# Sheet1.net
KiCad netlist of a schematic drawn in Altium Designer
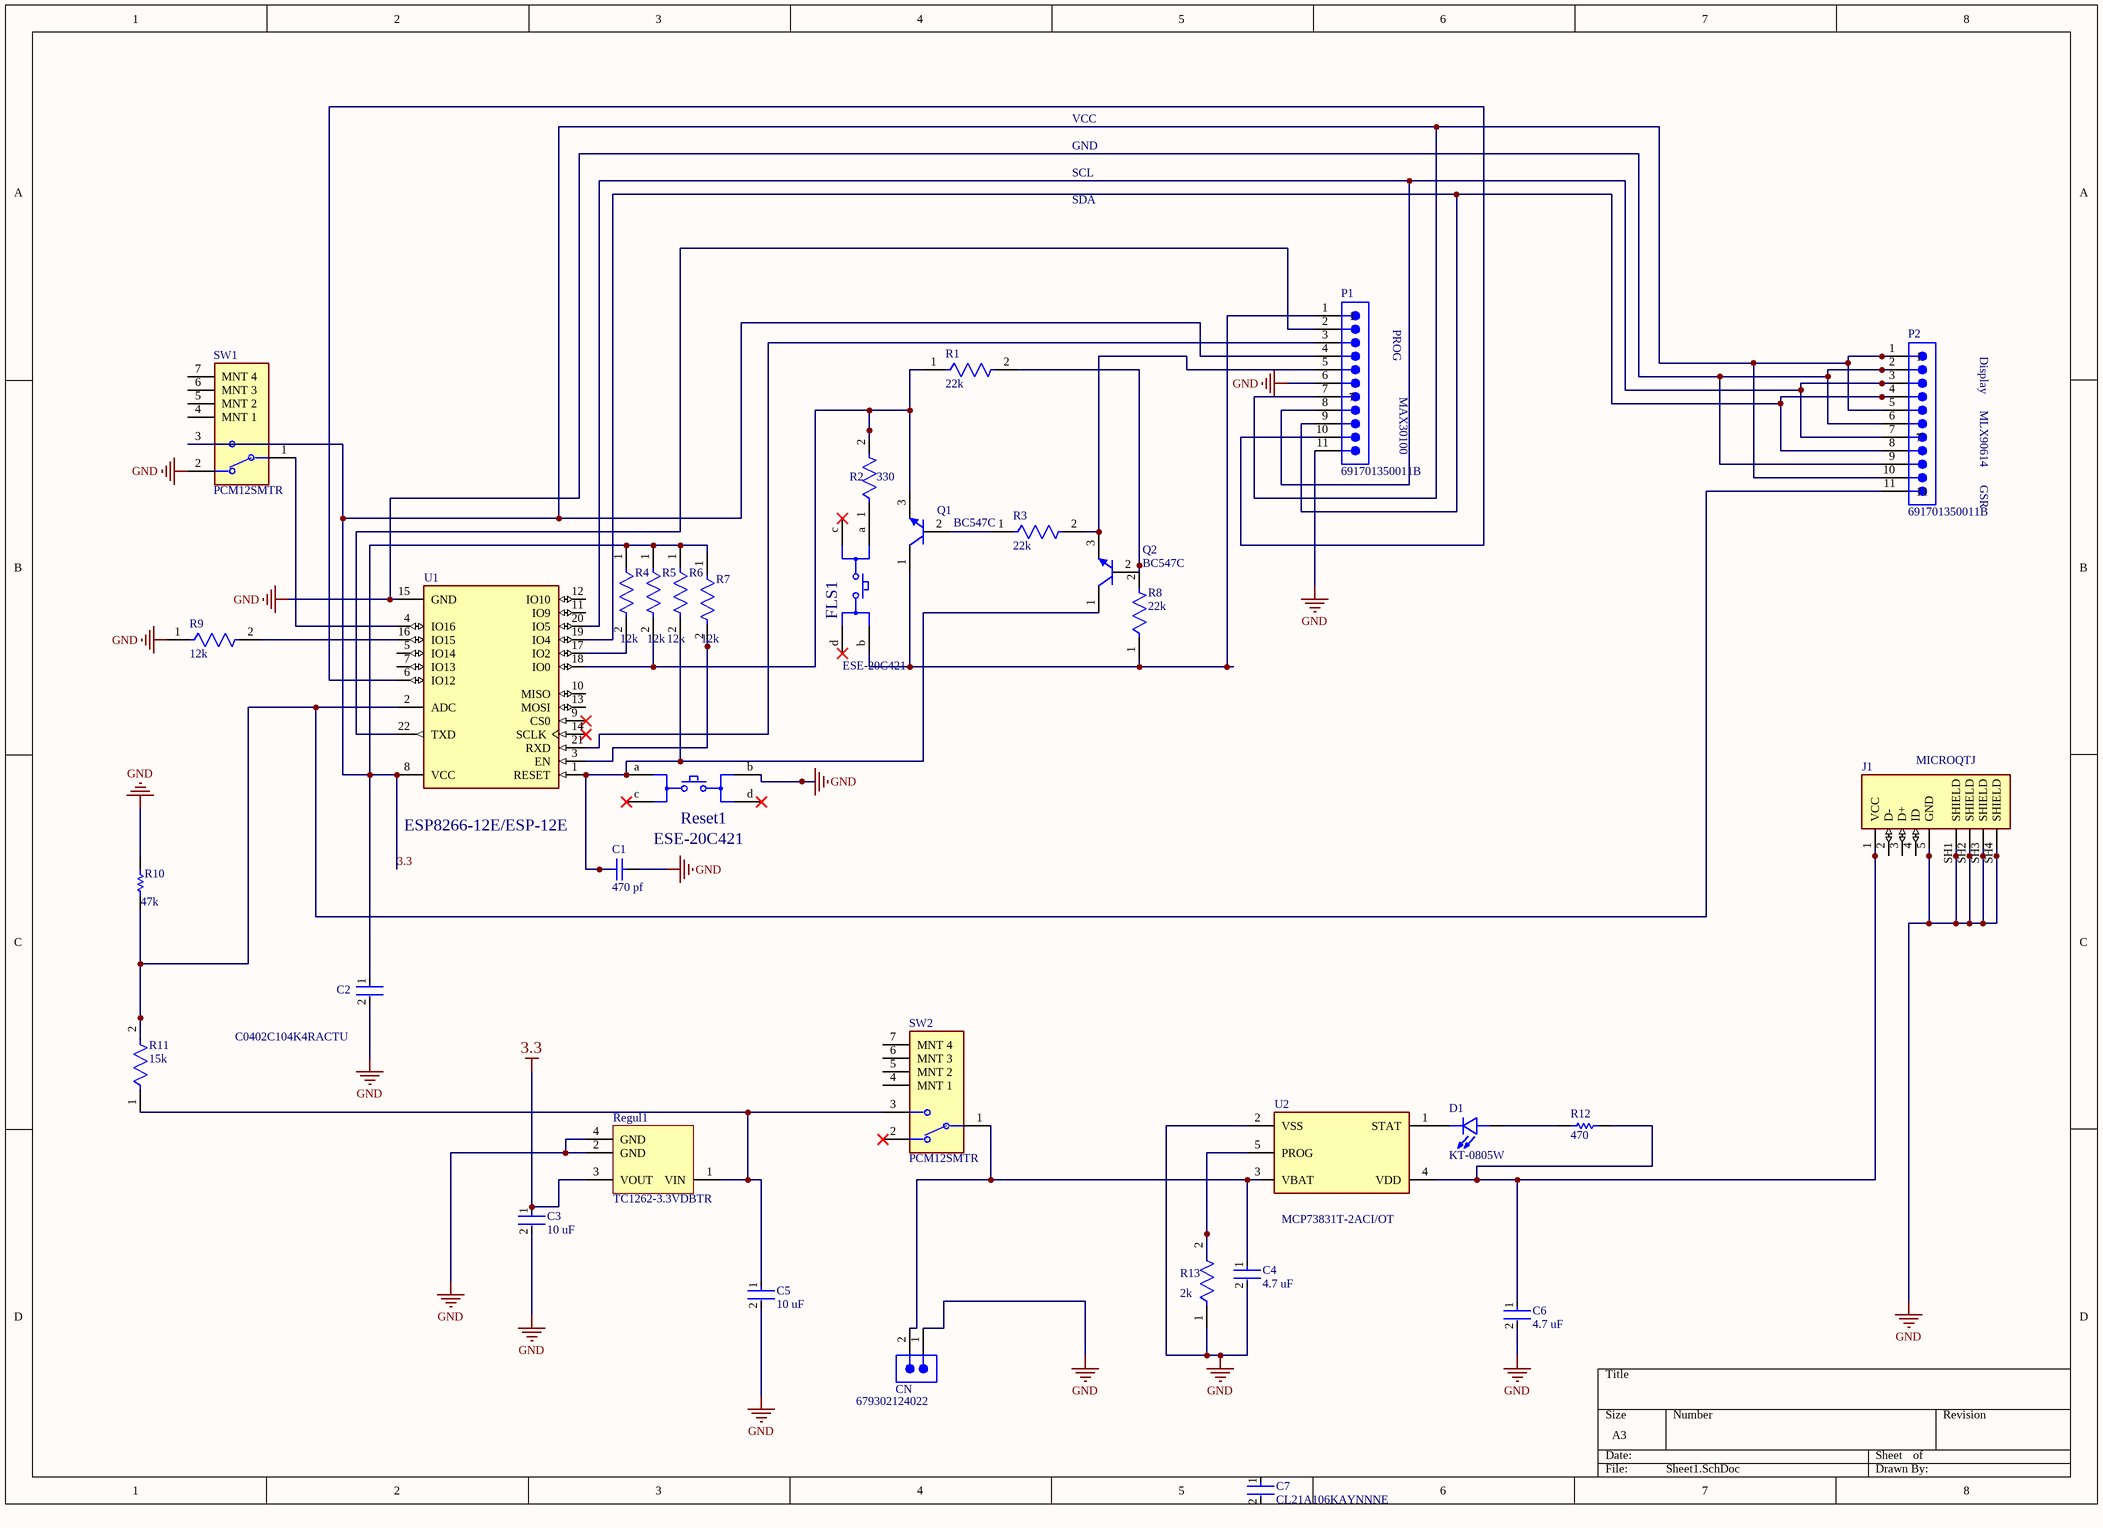
[diagram p0: Sheet1.SchDoc]

(export (version "E")
  (design (tool "Eeschema 10.0.6"))
  (components
    (comp (ref "C1")
      (value "470 pf")
      (footprint "CAPC2013X135X50LL15T20")
      (fields (field (name "MANUFACTURER") "Vitramon") (field (name "PART NUMBER") "VJ0805Y472KXACW1BC"))
      (libsource (lib "Altium Content Vault") (part "CAP"))
    )
    (comp (ref "C2")
      (value "C0402C104K4RACTU")
      (footprint "FP-C0402-BB-MFG")
      (description "CAP CER 0.1UF 16V X7R 0402")
      (fields
        (field (name "TOLERANCE") "0.1")
        (field (name "OCTOPART") "https://octopart.com/c0402c104k4ractu-kemet-94158")
      )
      (libsource (lib "Altium Content Vault") (part "b4654b650e69147ec39a6b967a45e02"))
    )
    (comp (ref "C3")
      (value "10 uF")
      (footprint "FP-CL21-IPC_A")
      (description "CL21 Series 0805 10uF 25V ±10% Tolerance X5R Multilayer Ceramic Chip Capacitor")
      (fields (field (name "TOLERANCE") "10%"))
      (libsource (lib "Altium Content Vault") (part "b4654b650e69147ec39a6b967a45e02"))
    )
    (comp (ref "C4")
      (value "4.7 uF")
      (footprint "FP-CL21-IPC_A")
      (description "CL21 Series 0805 4.7uF 25V ±10% Tolerance X5R Multilayer Ceramic Chip Capacitor")
      (fields (field (name "TOLERANCE") "10%"))
      (libsource (lib "Altium Content Vault") (part "b4654b650e69147ec39a6b967a45e02"))
    )
    (comp (ref "C5")
      (value "10 uF")
      (footprint "FP-CL21-IPC_A")
      (description "CL21 Series 0805 10uF 25V ±10% Tolerance X5R Multilayer Ceramic Chip Capacitor")
      (fields (field (name "TOLERANCE") "10%"))
      (libsource (lib "Altium Content Vault") (part "b4654b650e69147ec39a6b967a45e02"))
    )
    (comp (ref "C6")
      (value "4.7 uF")
      (footprint "FP-CL21-IPC_A")
      (description "CL21 Series 0805 4.7uF 25V ±10% Tolerance X5R Multilayer Ceramic Chip Capacitor")
      (fields (field (name "TOLERANCE") "10%"))
      (libsource (lib "Altium Content Vault") (part "b4654b650e69147ec39a6b967a45e02"))
    )
    (comp (ref "C7")
      (value "CL21A106KAYNNNE")
      (footprint "FP-CL21-IPC_A")
      (description "CL21 Series 0805 10uF 25V ±10% Tolerance X5R Multilayer Ceramic Chip Capacitor")
      (fields (field (name "TOLERANCE") "10%"))
      (libsource (lib "Altium Content Vault") (part "b4654b650e69147ec39a6b967a45e02"))
    )
    (comp (ref "CN")
      (value "679302124022")
      (footprint "679302124022")
      (libsource (lib "Altium Content Vault") (part "Header_Male_1R_02P"))
    )
    (comp (ref "D1")
      (value "KT-0805W")
      (footprint "LED_KT-0805W")
      (description "Light Emitting Diodes")
      (fields (field (name "MF") "Hubei KENTO Elec"))
      (libsource (lib "KT-0805W") (part "KT-0805W"))
    )
    (comp (ref "FLS1")
      (value "ESE-20C421")
      (footprint "FP-ESE-20C421-MFG")
      (description "SWITCH PUSH SPST-NO 0.1A 14V")
      (libsource (lib "Altium Content Vault") (part "eb2d96918082f90afa573f5ab447b27"))
    )
    (comp (ref "J1")
      (value "MICROQTJ")
      (footprint "SHOUHAN_MICROQTJ")
      (fields (field (name "MF") "shou han"))
      (libsource (lib "MICROQTJ") (part "MICROQTJ"))
    )
    (comp (ref "P1")
      (value "691701350011B")
      (footprint "691701350011B")
      (libsource (lib "Altium Content Vault") (part "TBL - 1R - 11P - Male"))
    )
    (comp (ref "P2")
      (value "691701350011B")
      (footprint "691701350011B")
      (libsource (lib "Altium Content Vault") (part "TBL - 1R - 11P - Male"))
    )
    (comp (ref "Q1")
      (value "BC547C")
      (footprint "ONSC-TO-92-3-29-11")
      (description "Amplifier Transistor, NPN Silicon, 3-Pin TO-92, Bulk Box")
      (fields (field (name "MANUFACTURER") "On Semiconductor"))
      (libsource (lib "Altium Content Vault") (part "ONSC-NPN-C1B2E3-3"))
    )
    (comp (ref "Q2")
      (value "BC547C")
      (footprint "ONSC-TO-92-3-29-11")
      (description "Amplifier Transistor, NPN Silicon, 3-Pin TO-92, Bulk Box")
      (fields (field (name "MANUFACTURER") "On Semiconductor"))
      (libsource (lib "Altium Content Vault") (part "ONSC-NPN-C1B2E3-3"))
    )
    (comp (ref "R1")
      (value "22k")
      (footprint "FP-CRCW0603-e3-IPC_B")
      (description "RES Thick Film, 22kΩ, 1%, 0.1W, 100ppm/°C, 0603")
      (fields (field (name "TOLERANCE") "1%"))
      (libsource (lib "Altium Content Vault") (part "1029c3af85768c4190bb7ad29bc67b5"))
    )
    (comp (ref "R2")
      (value "330")
      (footprint "FP-CRCW0402-e3-IPC_C")
      (description "RES Thick Film, 330kΩ, 1%, 0.063W, 100ppm/°C, 0402")
      (fields (field (name "TOLERANCE") "1%"))
      (libsource (lib "Altium Content Vault") (part "1029c3af85768c4190bb7ad29bc67b5"))
    )
    (comp (ref "R3")
      (value "22k")
      (footprint "FP-CRCW0603-e3-IPC_B")
      (description "RES Thick Film, 22kΩ, 1%, 0.1W, 100ppm/°C, 0603")
      (fields (field (name "TOLERANCE") "1%"))
      (libsource (lib "Altium Content Vault") (part "1029c3af85768c4190bb7ad29bc67b5"))
    )
    (comp (ref "R4")
      (value "12k")
      (footprint "FP-CRCW0603-e3-IPC_A")
      (description "RES Thick Film, 12kΩ, 1%, 0.1W, 100ppm/°C, 0603")
      (fields (field (name "TOLERANCE") "1%"))
      (libsource (lib "Altium Content Vault") (part "1029c3af85768c4190bb7ad29bc67b5"))
    )
    (comp (ref "R5")
      (value "12k")
      (footprint "FP-CRCW0603-e3-IPC_A")
      (description "RES Thick Film, 12kΩ, 1%, 0.1W, 100ppm/°C, 0603")
      (fields (field (name "TOLERANCE") "1%"))
      (libsource (lib "Altium Content Vault") (part "1029c3af85768c4190bb7ad29bc67b5"))
    )
    (comp (ref "R6")
      (value "12k")
      (footprint "FP-CRCW0603-e3-IPC_A")
      (description "RES Thick Film, 12kΩ, 1%, 0.1W, 100ppm/°C, 0603")
      (fields (field (name "TOLERANCE") "1%"))
      (libsource (lib "Altium Content Vault") (part "1029c3af85768c4190bb7ad29bc67b5"))
    )
    (comp (ref "R7")
      (value "12k")
      (footprint "FP-CRCW0603-e3-IPC_A")
      (description "RES Thick Film, 12kΩ, 1%, 0.1W, 100ppm/°C, 0603")
      (fields (field (name "TOLERANCE") "1%"))
      (libsource (lib "Altium Content Vault") (part "1029c3af85768c4190bb7ad29bc67b5"))
    )
    (comp (ref "R8")
      (value "22k")
      (footprint "FP-CRCW0603-e3-IPC_B")
      (description "RES Thick Film, 22kΩ, 1%, 0.1W, 100ppm/°C, 0603")
      (fields (field (name "TOLERANCE") "1%"))
      (libsource (lib "Altium Content Vault") (part "1029c3af85768c4190bb7ad29bc67b5"))
    )
    (comp (ref "R9")
      (value "12k")
      (footprint "FP-CRCW0603-e3-IPC_A")
      (description "RES Thick Film, 12kΩ, 1%, 0.1W, 100ppm/°C, 0603")
      (fields (field (name "TOLERANCE") "1%"))
      (libsource (lib "Altium Content Vault") (part "1029c3af85768c4190bb7ad29bc67b5"))
    )
    (comp (ref "R10")
      (value "47k")
      (footprint "RESC2013X70X40ML20T20")
      (fields (field (name "MANUFACTURER") "Panasonic") (field (name "PART NUMBER") "ERJ-6GEYJ473V"))
      (libsource (lib "Altium Content Vault") (part "RES"))
    )
    (comp (ref "R11")
      (value "15k")
      (footprint "FP-CRCW0805-e3-IPC_C")
      (description "RES Thick Film, 15kΩ, 1%, 0.125W, 100ppm/°C, 0805")
      (fields (field (name "TOLERANCE") "1%"))
      (libsource (lib "Altium Content Vault") (part "1029c3af85768c4190bb7ad29bc67b5"))
    )
    (comp (ref "R12")
      (value "470")
      (footprint "RESC2013X60X35LL10T20")
      (description "Chip Resistor, 470 Ohm, +/- 1%, 125 mW, -55 to 155 degC, 0805 (2012 Metric), RoHS, Tape and Reel")
      (fields (field (name "MANUFACTURER") "Yageo"))
      (libsource (lib "Altium Content Vault") (part "RES-2"))
    )
    (comp (ref "R13")
      (value "2k")
      (footprint "FP-AC0603-IPC_B")
      (description "RES 2kΩ 1.00% 0.1W 0603")
      (fields (field (name "TOLERANCE") "1%"))
      (libsource (lib "Altium Content Vault") (part "1029c3af85768c4190bb7ad29bc67b5"))
    )
    (comp (ref "Regul1")
      (value "TC1262-3.3VDBTR")
      (footprint "SOT-223-DB3_M")
      (description "500mA Fixed Output CMOS LDO, 3-Pin SOT-223, Extended Temperature, Tape and Reel")
      (libsource (lib "Altium Content Vault") (part "PM-LINEREG-TC1262-IL4"))
    )
    (comp (ref "Reset1")
      (value "ESE-20C421")
      (footprint "FP-ESE-20C421-MFG")
      (description "SWITCH PUSH SPST-NO 0.1A 14V")
      (libsource (lib "Altium Content Vault") (part "eb2d96918082f90afa573f5ab447b27"))
    )
    (comp (ref "SW1")
      (value "PCM12SMTR")
      (footprint "FP-PCM12SMTR-MFG")
      (description "SWITCH SLIDE SPDT 300MA 6V")
      (libsource (lib "Altium Content Vault") (part "1a3f67d7e2b5469b171eeab59ffb4d2"))
    )
    (comp (ref "SW2")
      (value "PCM12SMTR")
      (footprint "FP-PCM12SMTR-MFG")
      (description "SWITCH SLIDE SPDT 300MA 6V")
      (libsource (lib "Altium Content Vault") (part "1a3f67d7e2b5469b171eeab59ffb4d2"))
    )
    (comp (ref "U1")
      (value "ESP8266-12E/ESP-12E")
      (footprint "XCVR_ESP8266-12E/ESP-12E")
      (fields (field (name "MF") "AI-Thinker"))
      (libsource (lib "ESP8266-12E_ESP-12E (1)") (part "ESP8266-12E/ESP-12E"))
    )
    (comp (ref "U2")
      (value "MCP73831T-2ACI/OT")
      (footprint "FP-C04-091-OT-IPC_B")
      (description "IC CONTROLLR LI-ION 4.2V SOT23-5")
      (libsource (lib "Altium Content Vault") (part "61f5a3bb3429d9e0caadea342aa3b19"))
    )
  )
  (nets
    (net (code "1") (name "3.3") (class "Default")
      (node (ref "C2") (pin "1") (pinfunction "1_1") (pintype "passive"))
      (node (ref "C3") (pin "1") (pinfunction "1_1") (pintype "passive"))
      (node (ref "P1") (pin "4") (pinfunction "4_4") (pintype "passive"))
      (node (ref "P1") (pin "7") (pinfunction "7_7") (pintype "passive"))
      (node (ref "P2") (pin "1") (pinfunction "1_1") (pintype "passive"))
      (node (ref "P2") (pin "10") (pinfunction "10_10") (pintype "passive"))
      (node (ref "P2") (pin "5") (pinfunction "5_5") (pintype "passive"))
      (node (ref "R4") (pin "1") (pinfunction "1_1") (pintype "passive"))
      (node (ref "R5") (pin "1") (pinfunction "1_1") (pintype "passive"))
      (node (ref "R6") (pin "1") (pinfunction "1_1") (pintype "passive"))
      (node (ref "R7") (pin "1") (pinfunction "1_1") (pintype "passive"))
      (node (ref "Regul1") (pin "3") (pinfunction "VOUT_3") (pintype "power_in"))
      (node (ref "SW1") (pin "3") (pinfunction "3_3") (pintype "passive"))
      (node (ref "U1") (pin "8") (pinfunction "VCC_8") (pintype "power_in"))
    )
    (net (code "2") (name "GND") (class "Default")
      (node (ref "C1") (pin "2") (pinfunction "2_2") (pintype "passive"))
      (node (ref "C2") (pin "2") (pinfunction "2_2") (pintype "passive"))
      (node (ref "C3") (pin "2") (pinfunction "2_2") (pintype "passive"))
      (node (ref "C4") (pin "2") (pinfunction "2_2") (pintype "passive"))
      (node (ref "C5") (pin "2") (pinfunction "2_2") (pintype "passive"))
      (node (ref "C6") (pin "2") (pinfunction "2_2") (pintype "passive"))
      (node (ref "CN") (pin "1") (pinfunction "1_1") (pintype "passive"))
      (node (ref "J1") (pin "5") (pinfunction "GND_5") (pintype "power_in"))
      (node (ref "J1") (pin "SH1") (pinfunction "SHIELD_SH1") (pintype "passive"))
      (node (ref "J1") (pin "SH2") (pinfunction "SHIELD_SH2") (pintype "passive"))
      (node (ref "J1") (pin "SH3") (pinfunction "SHIELD_SH3") (pintype "passive"))
      (node (ref "J1") (pin "SH4") (pinfunction "SHIELD_SH4") (pintype "passive"))
      (node (ref "P1") (pin "11") (pinfunction "11_11") (pintype "passive"))
      (node (ref "P1") (pin "6") (pinfunction "6_6") (pintype "passive"))
      (node (ref "P2") (pin "2") (pinfunction "2_2") (pintype "passive"))
      (node (ref "P2") (pin "6") (pinfunction "6_6") (pintype "passive"))
      (node (ref "P2") (pin "9") (pinfunction "9_9") (pintype "passive"))
      (node (ref "R10") (pin "2") (pinfunction "2_2") (pintype "passive"))
      (node (ref "R13") (pin "1") (pinfunction "1_1") (pintype "passive"))
      (node (ref "R9") (pin "1") (pinfunction "1_1") (pintype "passive"))
      (node (ref "Regul1") (pin "2") (pinfunction "GND_2") (pintype "power_in"))
      (node (ref "Regul1") (pin "4") (pinfunction "GND_4") (pintype "power_in"))
      (node (ref "Reset1") (pin "b") (pinfunction "b_b") (pintype "passive"))
      (node (ref "SW1") (pin "2") (pinfunction "2_2") (pintype "passive"))
      (node (ref "U1") (pin "15") (pinfunction "GND_15") (pintype "power_in"))
      (node (ref "U2") (pin "2") (pinfunction "VSS_2") (pintype "power_in"))
    )
    (net (code "3") (name "Net-(D1-PadA)") (class "Default")
      (node (ref "D1") (pin "A") (pinfunction "A_A") (pintype "passive"))
      (node (ref "R12") (pin "1") (pinfunction "1_1") (pintype "passive"))
    )
    (net (code "4") (name "Net-(J1-VCC)") (class "Default")
      (node (ref "C6") (pin "1") (pinfunction "1_1") (pintype "passive"))
      (node (ref "J1") (pin "1") (pinfunction "VCC_1") (pintype "power_in"))
      (node (ref "R12") (pin "2") (pinfunction "2_2") (pintype "passive"))
      (node (ref "U2") (pin "4") (pinfunction "VDD_4") (pintype "power_in"))
    )
    (net (code "5") (name "Net-(Q1-B)") (class "Default")
      (node (ref "Q1") (pin "2") (pinfunction "B_2") (pintype "passive"))
      (node (ref "R3") (pin "1") (pinfunction "1_1") (pintype "passive"))
    )
    (net (code "6") (name "Net-(Q1-C)") (class "Default")
      (node (ref "FLS1") (pin "b") (pinfunction "b_b") (pintype "passive"))
      (node (ref "P1") (pin "1") (pinfunction "1_1") (pintype "passive"))
      (node (ref "Q1") (pin "1") (pinfunction "C_1") (pintype "passive"))
      (node (ref "R8") (pin "1") (pinfunction "1_1") (pintype "passive"))
    )
    (net (code "7") (name "Net-(Q1-E)") (class "Default")
      (node (ref "Q1") (pin "3") (pinfunction "E_3") (pintype "passive"))
      (node (ref "R1") (pin "1") (pinfunction "1_1") (pintype "passive"))
      (node (ref "R2") (pin "2") (pinfunction "2_2") (pintype "passive"))
      (node (ref "R5") (pin "2") (pinfunction "2_2") (pintype "passive"))
      (node (ref "U1") (pin "18") (pinfunction "IO0_18") (pintype "bidirectional"))
    )
    (net (code "8") (name "Net-(Q2-B)") (class "Default")
      (node (ref "Q2") (pin "2") (pinfunction "B_2") (pintype "passive"))
      (node (ref "R1") (pin "2") (pinfunction "2_2") (pintype "passive"))
      (node (ref "R8") (pin "2") (pinfunction "2_2") (pintype "passive"))
    )
    (net (code "9") (name "Net-(Q2-C)") (class "Default")
      (node (ref "C1") (pin "1") (pinfunction "1_1") (pintype "passive"))
      (node (ref "Q2") (pin "1") (pinfunction "C_1") (pintype "passive"))
      (node (ref "R6") (pin "2") (pinfunction "2_2") (pintype "passive"))
      (node (ref "Reset1") (pin "a") (pinfunction "a_a") (pintype "passive"))
      (node (ref "U1") (pin "1") (pinfunction "RESET_1") (pintype "input"))
    )
    (net (code "10") (name "Net-(Q2-E)") (class "Default")
      (node (ref "P1") (pin "5") (pinfunction "5_5") (pintype "passive"))
      (node (ref "Q2") (pin "3") (pinfunction "E_3") (pintype "passive"))
      (node (ref "R3") (pin "2") (pinfunction "2_2") (pintype "passive"))
    )
    (net (code "11") (name "Net-(Regul1-VIN)") (class "Default")
      (node (ref "C5") (pin "1") (pinfunction "1_1") (pintype "passive"))
      (node (ref "R11") (pin "1") (pinfunction "1_1") (pintype "passive"))
      (node (ref "Regul1") (pin "1") (pinfunction "VIN_1") (pintype "power_in"))
      (node (ref "SW2") (pin "3") (pinfunction "3_3") (pintype "passive"))
    )
    (net (code "12") (name "Net-(U1-ADC)") (class "Default")
      (node (ref "P2") (pin "11") (pinfunction "11_11") (pintype "passive"))
      (node (ref "R10") (pin "1") (pinfunction "1_1") (pintype "passive"))
      (node (ref "R11") (pin "2") (pinfunction "2_2") (pintype "passive"))
      (node (ref "U1") (pin "2") (pinfunction "ADC_2") (pintype "passive"))
    )
    (net (code "13") (name "Net-(U1-EN)") (class "Default")
      (node (ref "R7") (pin "2") (pinfunction "2_2") (pintype "passive"))
      (node (ref "U1") (pin "3") (pinfunction "EN_3") (pintype "input"))
    )
    (net (code "14") (name "Net-(U1-IO2)") (class "Default")
      (node (ref "R4") (pin "2") (pinfunction "2_2") (pintype "passive"))
      (node (ref "U1") (pin "17") (pinfunction "IO2_17") (pintype "bidirectional"))
    )
    (net (code "15") (name "Net-(U1-IO4)") (class "Default")
      (node (ref "P1") (pin "9") (pinfunction "9_9") (pintype "passive"))
      (node (ref "P2") (pin "4") (pinfunction "4_4") (pintype "passive"))
      (node (ref "P2") (pin "8") (pinfunction "8_8") (pintype "passive"))
      (node (ref "U1") (pin "19") (pinfunction "IO4_19") (pintype "bidirectional"))
    )
    (net (code "16") (name "Net-(U1-IO5)") (class "Default")
      (node (ref "P1") (pin "8") (pinfunction "8_8") (pintype "passive"))
      (node (ref "P2") (pin "3") (pinfunction "3_3") (pintype "passive"))
      (node (ref "P2") (pin "7") (pinfunction "7_7") (pintype "passive"))
      (node (ref "U1") (pin "20") (pinfunction "IO5_20") (pintype "bidirectional"))
    )
    (net (code "17") (name "Net-(U1-IO12)") (class "Default")
      (node (ref "P1") (pin "10") (pinfunction "10_10") (pintype "passive"))
      (node (ref "U1") (pin "6") (pinfunction "IO12_6") (pintype "bidirectional"))
    )
    (net (code "18") (name "Net-(U1-IO15)") (class "Default")
      (node (ref "R9") (pin "2") (pinfunction "2_2") (pintype "passive"))
      (node (ref "U1") (pin "16") (pinfunction "IO15_16") (pintype "bidirectional"))
    )
    (net (code "19") (name "Net-(U1-IO16)") (class "Default")
      (node (ref "SW1") (pin "1") (pinfunction "1_1") (pintype "passive"))
      (node (ref "U1") (pin "4") (pinfunction "IO16_4") (pintype "bidirectional"))
    )
    (net (code "20") (name "Net-(U1-RXD)") (class "Default")
      (node (ref "P1") (pin "3") (pinfunction "3_3") (pintype "passive"))
      (node (ref "U1") (pin "21") (pinfunction "RXD_21") (pintype "input"))
    )
    (net (code "21") (name "Net-(U1-TXD)") (class "Default")
      (node (ref "P1") (pin "2") (pinfunction "2_2") (pintype "passive"))
      (node (ref "U1") (pin "22") (pinfunction "TXD_22") (pintype "output"))
    )
    (net (code "22") (name "Net-(U2-PROG)") (class "Default")
      (node (ref "R13") (pin "2") (pinfunction "2_2") (pintype "passive"))
      (node (ref "U2") (pin "5") (pinfunction "PROG_5") (pintype "passive"))
    )
    (net (code "23") (name "Net-(U2-STAT)") (class "Default")
      (node (ref "D1") (pin "C") (pinfunction "C_C") (pintype "passive"))
      (node (ref "U2") (pin "1") (pinfunction "STAT_1") (pintype "passive"))
    )
    (net (code "24") (name "Net-(U2-VBAT)") (class "Default")
      (node (ref "C4") (pin "1") (pinfunction "1_1") (pintype "passive"))
      (node (ref "CN") (pin "2") (pinfunction "2_2") (pintype "passive"))
      (node (ref "SW2") (pin "1") (pinfunction "1_1") (pintype "passive"))
      (node (ref "U2") (pin "3") (pinfunction "VBAT_3") (pintype "power_in"))
    )
    (net (code "25") (name "unconnected-(C7-Pad1)") (class "Default")
      (node (ref "C7") (pin "1") (pinfunction "1_1") (pintype "passive"))
    )
    (net (code "26") (name "unconnected-(C7-Pad2)") (class "Default")
      (node (ref "C7") (pin "2") (pinfunction "2_2") (pintype "passive"))
    )
    (net (code "27") (name "unconnected-(FLS1-Pada)") (class "Default")
      (node (ref "FLS1") (pin "a") (pinfunction "a_a") (pintype "passive"))
    )
    (net (code "28") (name "unconnected-(FLS1-Padc)") (class "Default")
      (node (ref "FLS1") (pin "c") (pinfunction "c_c") (pintype "passive+no_connect"))
    )
    (net (code "29") (name "unconnected-(FLS1-Padd)") (class "Default")
      (node (ref "FLS1") (pin "d") (pinfunction "d_d") (pintype "passive+no_connect"))
    )
    (net (code "30") (name "unconnected-(J1-D+-Pad3)") (class "Default")
      (node (ref "J1") (pin "3") (pinfunction "D+_3") (pintype "bidirectional"))
    )
    (net (code "31") (name "unconnected-(J1-D--Pad2)") (class "Default")
      (node (ref "J1") (pin "2") (pinfunction "D-_2") (pintype "bidirectional"))
    )
    (net (code "32") (name "unconnected-(J1-ID-Pad4)") (class "Default")
      (node (ref "J1") (pin "4") (pinfunction "ID_4") (pintype "bidirectional"))
    )
    (net (code "33") (name "unconnected-(R2-Pad1)") (class "Default")
      (node (ref "R2") (pin "1") (pinfunction "1_1") (pintype "passive"))
    )
    (net (code "34") (name "unconnected-(Reset1-Padc)") (class "Default")
      (node (ref "Reset1") (pin "c") (pinfunction "c_c") (pintype "passive+no_connect"))
    )
    (net (code "35") (name "unconnected-(Reset1-Padd)") (class "Default")
      (node (ref "Reset1") (pin "d") (pinfunction "d_d") (pintype "passive+no_connect"))
    )
    (net (code "36") (name "unconnected-(SW1-MNT_1-Pad4)") (class "Default")
      (node (ref "SW1") (pin "4") (pinfunction "MNT_1_4") (pintype "passive"))
    )
    (net (code "37") (name "unconnected-(SW1-MNT_2-Pad5)") (class "Default")
      (node (ref "SW1") (pin "5") (pinfunction "MNT_2_5") (pintype "passive"))
    )
    (net (code "38") (name "unconnected-(SW1-MNT_3-Pad6)") (class "Default")
      (node (ref "SW1") (pin "6") (pinfunction "MNT_3_6") (pintype "passive"))
    )
    (net (code "39") (name "unconnected-(SW1-MNT_4-Pad7)") (class "Default")
      (node (ref "SW1") (pin "7") (pinfunction "MNT_4_7") (pintype "passive"))
    )
    (net (code "40") (name "unconnected-(SW2-MNT_1-Pad4)") (class "Default")
      (node (ref "SW2") (pin "4") (pinfunction "MNT_1_4") (pintype "passive"))
    )
    (net (code "41") (name "unconnected-(SW2-MNT_2-Pad5)") (class "Default")
      (node (ref "SW2") (pin "5") (pinfunction "MNT_2_5") (pintype "passive"))
    )
    (net (code "42") (name "unconnected-(SW2-MNT_3-Pad6)") (class "Default")
      (node (ref "SW2") (pin "6") (pinfunction "MNT_3_6") (pintype "passive"))
    )
    (net (code "43") (name "unconnected-(SW2-MNT_4-Pad7)") (class "Default")
      (node (ref "SW2") (pin "7") (pinfunction "MNT_4_7") (pintype "passive"))
    )
    (net (code "44") (name "unconnected-(SW2-Pad2)") (class "Default")
      (node (ref "SW2") (pin "2") (pinfunction "2_2") (pintype "passive+no_connect"))
    )
    (net (code "45") (name "unconnected-(U1-CS0-Pad9)") (class "Default")
      (node (ref "U1") (pin "9") (pinfunction "CS0_9") (pintype "input+no_connect"))
    )
    (net (code "46") (name "unconnected-(U1-IO9-Pad11)") (class "Default")
      (node (ref "U1") (pin "11") (pinfunction "IO9_11") (pintype "bidirectional"))
    )
    (net (code "47") (name "unconnected-(U1-IO10-Pad12)") (class "Default")
      (node (ref "U1") (pin "12") (pinfunction "IO10_12") (pintype "bidirectional"))
    )
    (net (code "48") (name "unconnected-(U1-IO13-Pad7)") (class "Default")
      (node (ref "U1") (pin "7") (pinfunction "IO13_7") (pintype "bidirectional"))
    )
    (net (code "49") (name "unconnected-(U1-IO14-Pad5)") (class "Default")
      (node (ref "U1") (pin "5") (pinfunction "IO14_5") (pintype "bidirectional"))
    )
    (net (code "50") (name "unconnected-(U1-MISO-Pad10)") (class "Default")
      (node (ref "U1") (pin "10") (pinfunction "MISO_10") (pintype "bidirectional"))
    )
    (net (code "51") (name "unconnected-(U1-MOSI-Pad13)") (class "Default")
      (node (ref "U1") (pin "13") (pinfunction "MOSI_13") (pintype "bidirectional"))
    )
    (net (code "52") (name "unconnected-(U1-SCLK-Pad14)") (class "Default")
      (node (ref "U1") (pin "14") (pinfunction "SCLK_14") (pintype "input+no_connect"))
    )
  )
)
